# USBToTTL.net
KiCad netlist of a schematic drawn in Altium Designer
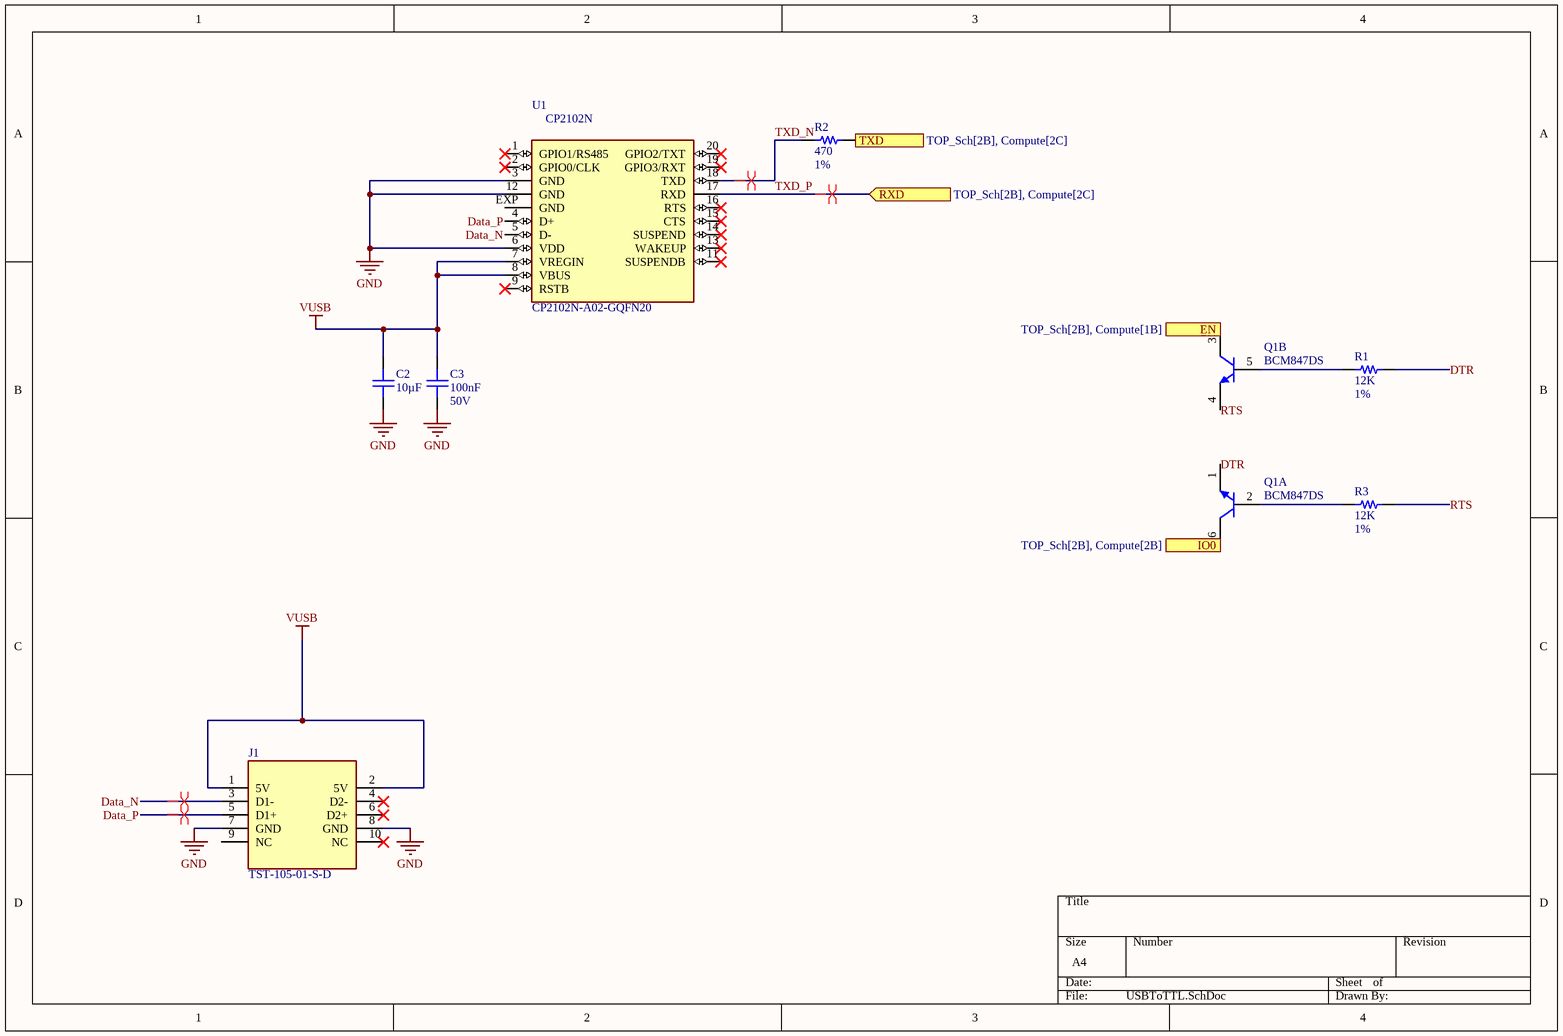
[diagram p0: USBToTTL.SchDoc]

(export (version "E")
  (design (tool "Eeschema 10.0.6"))
  (components
    (comp (ref "C2")
      (value "10µF")
      (footprint "FP-GRM188-0_2-IPC_B")
      (fields (field (name "Comment") "GRM188R61E106MA73J"))
      (libsource (lib "ILH") (part "Capacitor Voltage Rating"))
    )
    (comp (ref "C3")
      (value "100nF")
      (footprint "CAPC1608X90X35LL15T15")
      (fields
        (field (name "VOLTAGE RATING") "50V")
        (field (name "TOLERANCE") "10%")
        (field (name "Comment") "06035C104KAT4A")
      )
      (libsource (lib "ILH") (part "Capacitor Voltage Rating"))
    )
    (comp (ref "J1")
      (value "TST-105-01-S-D")
      (footprint "TST-105-01-S-D-Footprint-1")
      (libsource (lib "ILH") (part "TST-105-01-S-D-Symbol-1"))
    )
    (comp (ref "Q1")
      (value "BCM847DS")
      (footprint "SOT95P275X110-6N")
      (description "Trans GP BJT NPN 45V 0.1A 6-Pin TSOP T/R")
      (fields (field (name "SOURCE") "SiCeff_Parameter_V2.SCHLIB"))
      (libsource (lib "ILH") (part "BCM847DS"))
    )
    (comp (ref "R1")
      (value "12K")
      (footprint "RESC1608X06L 0603 High Density")
      (description "SMD Chip Resistor, 18 kOhm, ± 1%, 100 mW, 0603 [1608 Metric], Thick Film, General Purpose")
      (fields
        (field (name "TOLERANCE") "1%")
        (field (name "POWER") "100mW")
        (field (name "Comment") "RC0603FR-0718KL")
      )
      (libsource (lib "ILH") (part "Resistor Tolerance"))
    )
    (comp (ref "R2")
      (value "470")
      (footprint "RESC1608X06L 0603 High Density")
      (description "Res Thick Film 0603 470 Ohm 1% 0.1W(1/10W) ±100ppm/C Pad SMD T/R")
      (fields
        (field (name "TOLERANCE") "1%")
        (field (name "POWER") "100mW")
        (field (name "Comment") "RC0603FR-07470RL")
      )
      (libsource (lib "ILH") (part "Resistor Tolerance"))
    )
    (comp (ref "R3")
      (value "12K")
      (footprint "RESC1608X06L 0603 High Density")
      (description "SMD Chip Resistor, 18 kOhm, ± 1%, 100 mW, 0603 [1608 Metric], Thick Film, General Purpose")
      (fields
        (field (name "TOLERANCE") "1%")
        (field (name "POWER") "100mW")
        (field (name "Comment") "RC0603FR-0718KL")
      )
      (libsource (lib "ILH") (part "Resistor Tolerance"))
    )
    (comp (ref "U1")
      (value "CP2102N-A02-GQFN20")
      (footprint "WFQFN-20")
      (description "USB Bridge, USB to UART USB 2.0 UART Interface 20-QFN (3x3)")
      (fields (field (name "MF") "Silicon Labs"))
      (libsource (lib "CP2102N-A02-GQFN20") (part "CP2102N-A02-GQFN20"))
    )
  )
  (nets
    (net (code "1") (name "/DTR") (class "Default")
      (node (ref "Q1") (pin "1") (pinfunction "E_1") (pintype "passive"))
      (node (ref "R1") (pin "2") (pinfunction "2_2") (pintype "passive"))
    )
    (net (code "2") (name "/Data_N") (class "Default")
      (node (ref "J1") (pin "3") (pinfunction "D1-_3") (pintype "passive"))
      (node (ref "U1") (pin "5") (pinfunction "D-_5") (pintype "bidirectional"))
    )
    (net (code "3") (name "/Data_P") (class "Default")
      (node (ref "J1") (pin "5") (pinfunction "D1+_5") (pintype "passive"))
      (node (ref "U1") (pin "4") (pinfunction "D+_4") (pintype "bidirectional"))
    )
    (net (code "4") (name "/EN") (class "Default")
      (node (ref "Q1") (pin "3") (pinfunction "C_3") (pintype "passive"))
    )
    (net (code "5") (name "/IO0") (class "Default")
      (node (ref "Q1") (pin "6") (pinfunction "C_6") (pintype "passive"))
    )
    (net (code "6") (name "/RTS") (class "Default")
      (node (ref "Q1") (pin "4") (pinfunction "E_4") (pintype "passive"))
      (node (ref "R3") (pin "2") (pinfunction "2_2") (pintype "passive"))
    )
    (net (code "7") (name "/TXD") (class "Default")
      (node (ref "R2") (pin "2") (pinfunction "2_2") (pintype "passive"))
    )
    (net (code "8") (name "/TXD_N") (class "Default")
      (node (ref "R2") (pin "1") (pinfunction "1_1") (pintype "passive"))
      (node (ref "U1") (pin "18") (pinfunction "TXD_18") (pintype "bidirectional"))
    )
    (net (code "9") (name "/TXD_P") (class "Default")
      (node (ref "U1") (pin "17") (pinfunction "RXD_17") (pintype "passive"))
    )
    (net (code "10") (name "GND") (class "Default")
      (node (ref "C2") (pin "1") (pinfunction "1_1") (pintype "passive"))
      (node (ref "C3") (pin "1") (pinfunction "1_1") (pintype "passive"))
      (node (ref "J1") (pin "7") (pinfunction "GND_7") (pintype "passive"))
      (node (ref "J1") (pin "8") (pinfunction "GND_8") (pintype "passive"))
      (node (ref "U1") (pin "12") (pinfunction "GND_12") (pintype "passive"))
      (node (ref "U1") (pin "3") (pinfunction "GND_3") (pintype "passive"))
      (node (ref "U1") (pin "6") (pinfunction "VDD_6") (pintype "bidirectional"))
    )
    (net (code "11") (name "Net-(Q1A-B)") (class "Default")
      (node (ref "Q1") (pin "2") (pinfunction "B_2") (pintype "passive"))
      (node (ref "R3") (pin "1") (pinfunction "1_1") (pintype "passive"))
    )
    (net (code "12") (name "Net-(Q1B-B)") (class "Default")
      (node (ref "Q1") (pin "5") (pinfunction "B_5") (pintype "passive"))
      (node (ref "R1") (pin "1") (pinfunction "1_1") (pintype "passive"))
    )
    (net (code "13") (name "VUSB") (class "Default")
      (node (ref "C2") (pin "2") (pinfunction "2_2") (pintype "passive"))
      (node (ref "C3") (pin "2") (pinfunction "2_2") (pintype "passive"))
      (node (ref "J1") (pin "1") (pinfunction "5V_1") (pintype "passive"))
      (node (ref "J1") (pin "2") (pinfunction "5V_2") (pintype "passive"))
      (node (ref "U1") (pin "7") (pinfunction "VREGIN_7") (pintype "bidirectional"))
      (node (ref "U1") (pin "8") (pinfunction "VBUS_8") (pintype "bidirectional"))
    )
    (net (code "14") (name "unconnected-(J1-D2+-Pad6)") (class "Default")
      (node (ref "J1") (pin "6") (pinfunction "D2+_6") (pintype "passive+no_connect"))
    )
    (net (code "15") (name "unconnected-(J1-D2--Pad4)") (class "Default")
      (node (ref "J1") (pin "4") (pinfunction "D2-_4") (pintype "passive+no_connect"))
    )
    (net (code "16") (name "unconnected-(J1-NC-Pad9)") (class "Default")
      (node (ref "J1") (pin "9") (pinfunction "NC_9") (pintype "passive"))
    )
    (net (code "17") (name "unconnected-(J1-NC-Pad10)") (class "Default")
      (node (ref "J1") (pin "10") (pinfunction "NC_10") (pintype "passive+no_connect"))
    )
    (net (code "18") (name "unconnected-(U1-CTS-Pad15)") (class "Default")
      (node (ref "U1") (pin "15") (pinfunction "CTS_15") (pintype "bidirectional+no_connect"))
    )
    (net (code "19") (name "unconnected-(U1-GND-PadEXP)") (class "Default")
      (node (ref "U1") (pin "EXP") (pinfunction "GND_EXP") (pintype "passive"))
    )
    (net (code "20") (name "unconnected-(U1-GPIO0{slash}CLK-Pad2)") (class "Default")
      (node (ref "U1") (pin "2") (pinfunction "GPIO0/CLK_2") (pintype "bidirectional+no_connect"))
    )
    (net (code "21") (name "unconnected-(U1-GPIO1{slash}RS485-Pad1)") (class "Default")
      (node (ref "U1") (pin "1") (pinfunction "GPIO1/RS485_1") (pintype "bidirectional+no_connect"))
    )
    (net (code "22") (name "unconnected-(U1-GPIO2{slash}TXT-Pad20)") (class "Default")
      (node (ref "U1") (pin "20") (pinfunction "GPIO2/TXT_20") (pintype "bidirectional+no_connect"))
    )
    (net (code "23") (name "unconnected-(U1-GPIO3{slash}RXT-Pad19)") (class "Default")
      (node (ref "U1") (pin "19") (pinfunction "GPIO3/RXT_19") (pintype "bidirectional+no_connect"))
    )
    (net (code "24") (name "unconnected-(U1-RSTB-Pad9)") (class "Default")
      (node (ref "U1") (pin "9") (pinfunction "RSTB_9") (pintype "bidirectional+no_connect"))
    )
    (net (code "25") (name "unconnected-(U1-RTS-Pad16)") (class "Default")
      (node (ref "U1") (pin "16") (pinfunction "RTS_16") (pintype "bidirectional+no_connect"))
    )
    (net (code "26") (name "unconnected-(U1-SUSPEND-Pad14)") (class "Default")
      (node (ref "U1") (pin "14") (pinfunction "SUSPEND_14") (pintype "bidirectional+no_connect"))
    )
    (net (code "27") (name "unconnected-(U1-SUSPENDB-Pad11)") (class "Default")
      (node (ref "U1") (pin "11") (pinfunction "SUSPENDB_11") (pintype "bidirectional+no_connect"))
    )
    (net (code "28") (name "unconnected-(U1-WAKEUP-Pad13)") (class "Default")
      (node (ref "U1") (pin "13") (pinfunction "WAKEUP_13") (pintype "bidirectional+no_connect"))
    )
  )
)
